# ADS7822.net
KiCad netlist of a schematic drawn in EAGLE
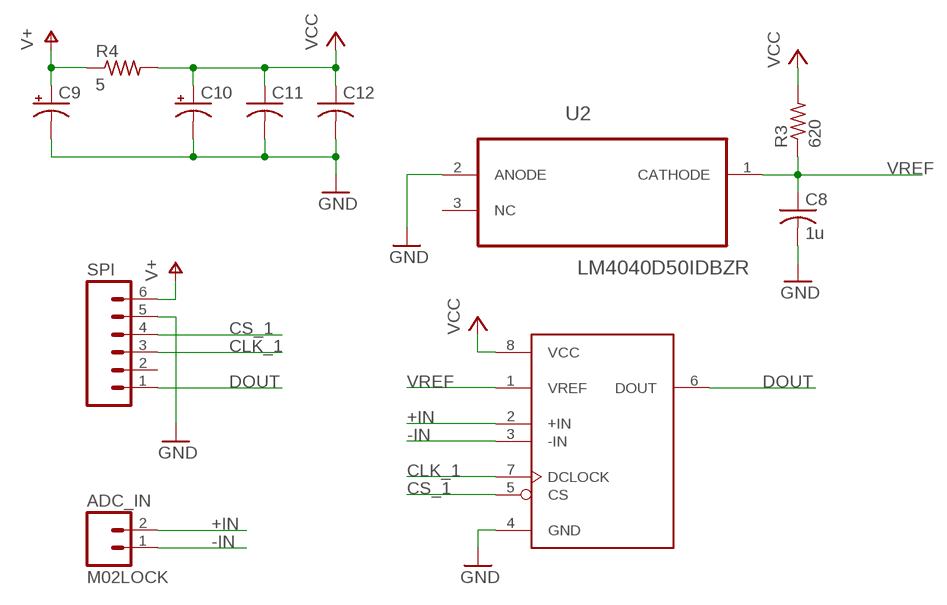
[diagram p0: schematic, sheet 2]

(export (version "E")
  (design (tool "Eeschema 10.0.6"))
  (components
    (comp (ref "ADC_IN")
      (value "M02LOCK")
      (footprint "eagle-import:1X02_LOCK")
      (libsource (lib "eagle-import") (part "M02LOCK"))
    )
    (comp (ref "C8")
      (value "1u")
      (footprint "eagle-import:C0805")
      (libsource (lib "eagle-import") (part "C-USC0805"))
    )
    (comp (ref "C9")
      (value "CPOL-US")
      (footprint "eagle-import:SMD_6.6X6.6")
      (libsource (lib "eagle-import") (part "CPOL-US"))
    )
    (comp (ref "C10")
      (value "CPOL-US")
      (footprint "eagle-import:SMD_6.6X6.6")
      (libsource (lib "eagle-import") (part "CPOL-US"))
    )
    (comp (ref "C11")
      (value "C-USC0805")
      (footprint "eagle-import:C0805")
      (libsource (lib "eagle-import") (part "C-USC0805"))
    )
    (comp (ref "C12")
      (value "C-USC0805")
      (footprint "eagle-import:C0805")
      (libsource (lib "eagle-import") (part "C-USC0805"))
    )
    (comp (ref "R3")
      (value "620")
      (footprint "eagle-import:R0805")
      (libsource (lib "eagle-import") (part "R-US_R0805"))
    )
    (comp (ref "R4")
      (value "5")
      (footprint "eagle-import:R1206")
      (libsource (lib "eagle-import") (part "R-US_R1206"))
    )
    (comp (ref "SPI")
      (value "M06LOCK")
      (footprint "eagle-import:1X06_LOCK")
      (libsource (lib "eagle-import") (part "M06LOCK"))
    )
    (comp (ref "U$3")
      (value "ADS7822")
      (footprint "eagle-import:SO-08")
      (libsource (lib "eagle-import") (part "ADS7822"))
    )
    (comp (ref "U2")
      (value "LM4040D50IDBZR")
      (footprint "eagle-import:SOT95P237X112-3N")
      (libsource (lib "eagle-import") (part "LM4040D50IDBZR"))
    )
  )
  (nets
    (net (code "1") (name "+IN") (class "Default")
      (node (ref "ADC_IN") (pin "2") (pinfunction "2_2") (pintype "passive"))
      (node (ref "U$3") (pin "2") (pinfunction "+IN_2") (pintype "input"))
    )
    (net (code "2") (name "-IN") (class "Default")
      (node (ref "ADC_IN") (pin "1") (pinfunction "1_1") (pintype "passive"))
      (node (ref "U$3") (pin "3") (pinfunction "-IN_3") (pintype "input"))
    )
    (net (code "3") (name "CLK_1") (class "Default")
      (node (ref "SPI") (pin "3") (pinfunction "3_3") (pintype "passive"))
      (node (ref "U$3") (pin "7") (pinfunction "DCLOCK_7") (pintype "input"))
    )
    (net (code "4") (name "CS_1") (class "Default")
      (node (ref "SPI") (pin "4") (pinfunction "4_4") (pintype "passive"))
      (node (ref "U$3") (pin "5") (pinfunction "CS_5") (pintype "input"))
    )
    (net (code "5") (name "DOUT") (class "Default")
      (node (ref "SPI") (pin "1") (pinfunction "1_1") (pintype "passive"))
      (node (ref "U$3") (pin "6") (pinfunction "DOUT_6") (pintype "output"))
    )
    (net (code "6") (name "GND") (class "Default")
      (node (ref "C10") (pin "-") (pinfunction "-_-") (pintype "passive"))
      (node (ref "C11") (pin "2") (pinfunction "2_2") (pintype "passive"))
      (node (ref "C12") (pin "2") (pinfunction "2_2") (pintype "passive"))
      (node (ref "C8") (pin "2") (pinfunction "2_2") (pintype "passive"))
      (node (ref "C9") (pin "-") (pinfunction "-_-") (pintype "passive"))
      (node (ref "SPI") (pin "5") (pinfunction "5_5") (pintype "passive"))
      (node (ref "U$3") (pin "4") (pinfunction "GND_4") (pintype "power_in"))
      (node (ref "U2") (pin "2") (pinfunction "ANODE_2") (pintype "input"))
    )
    (net (code "7") (name "V+") (class "Default")
      (node (ref "C9") (pin "+") (pinfunction "+_+") (pintype "passive"))
      (node (ref "R4") (pin "1") (pinfunction "1_1") (pintype "passive"))
      (node (ref "SPI") (pin "6") (pinfunction "6_6") (pintype "passive"))
    )
    (net (code "8") (name "VCC") (class "Default")
      (node (ref "C10") (pin "+") (pinfunction "+_+") (pintype "passive"))
      (node (ref "C11") (pin "1") (pinfunction "1_1") (pintype "passive"))
      (node (ref "C12") (pin "1") (pinfunction "1_1") (pintype "passive"))
      (node (ref "R3") (pin "2") (pinfunction "2_2") (pintype "passive"))
      (node (ref "R4") (pin "2") (pinfunction "2_2") (pintype "passive"))
      (node (ref "U$3") (pin "8") (pinfunction "VCC_8") (pintype "power_in"))
    )
    (net (code "9") (name "VREF") (class "Default")
      (node (ref "C8") (pin "1") (pinfunction "1_1") (pintype "passive"))
      (node (ref "R3") (pin "1") (pinfunction "1_1") (pintype "passive"))
      (node (ref "U$3") (pin "1") (pinfunction "VREF_1") (pintype "input"))
      (node (ref "U2") (pin "1") (pinfunction "CATHODE_1") (pintype "output"))
    )
    (net (code "10") (name "unconnected-(SPI-Pad2)") (class "Default")
      (node (ref "SPI") (pin "2") (pinfunction "2_2") (pintype "passive"))
    )
    (net (code "11") (name "unconnected-(U2-NC-Pad3)") (class "Default")
      (node (ref "U2") (pin "3") (pinfunction "NC_3") (pintype "no_connect"))
    )
  )
)
